# Output_Rele.net
KiCad netlist of a schematic drawn in Altium Designer
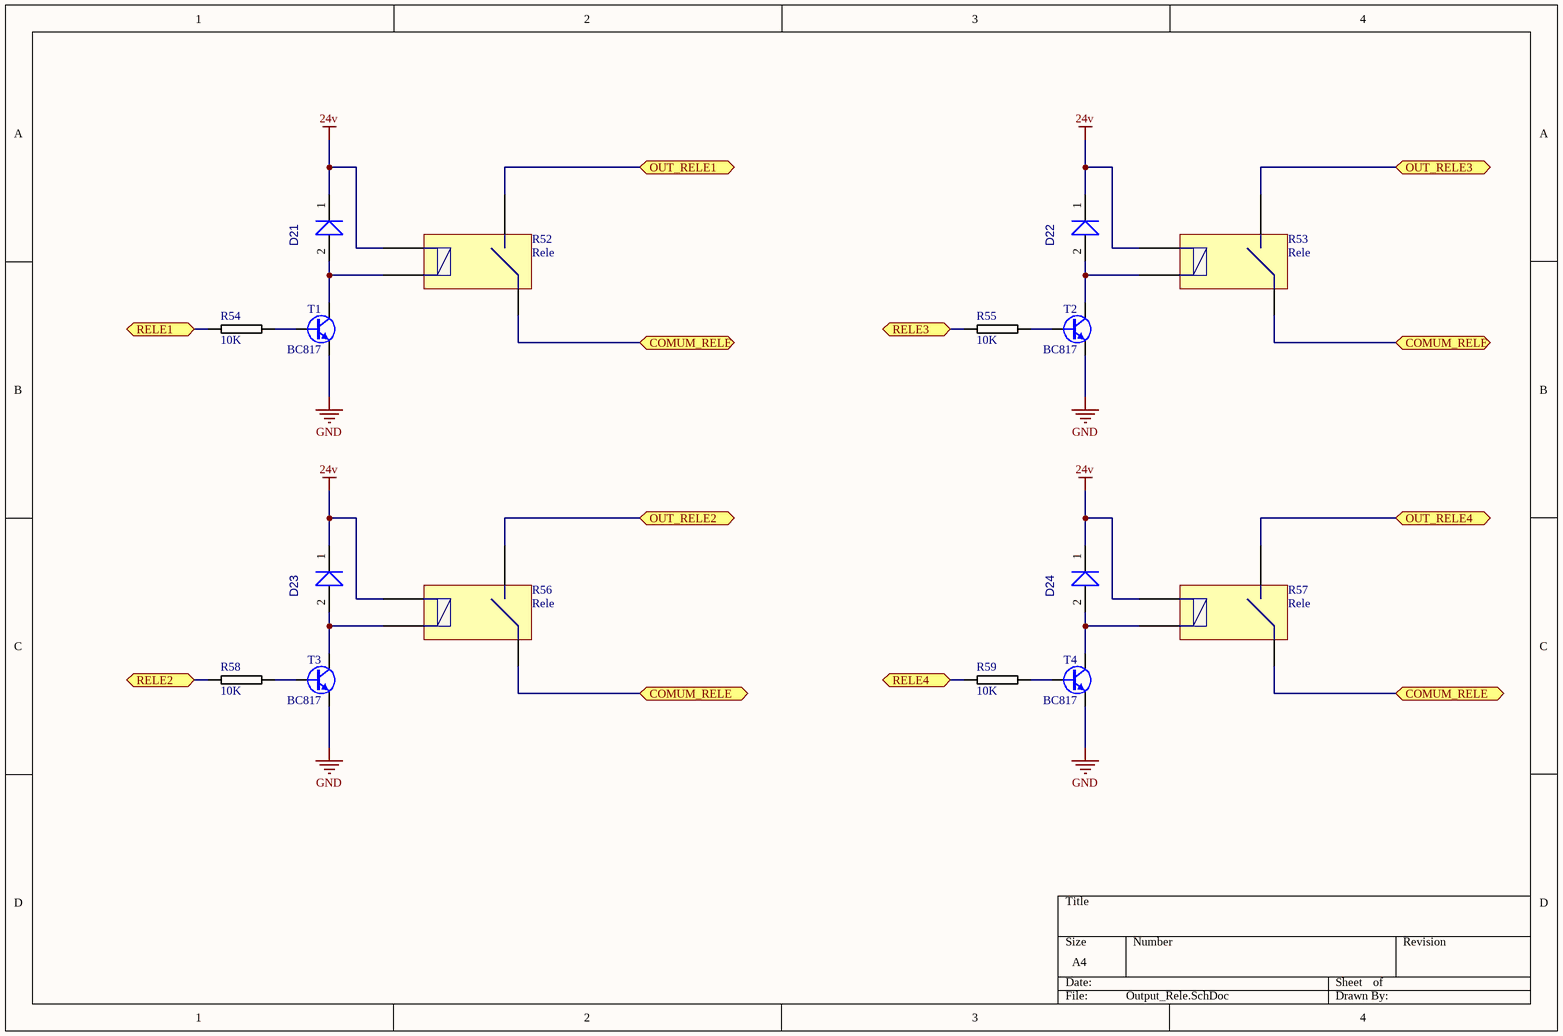
[diagram p0: Output_Rele.SchDoc]

(export (version "E")
  (design (tool "Eeschema 10.0.6"))
  (components
    (comp (ref "D21")
      (value "DIODO 1N4007 PF-B1")
      (footprint "DIODO DO41 PF-B1")
      (libsource (lib "GNATUS_COMPONENTES_BASE") (part "DIODO 1N4007 PF-B1"))
    )
    (comp (ref "D22")
      (value "DIODO 1N4007 PF-B1")
      (footprint "DIODO DO41 PF-B1")
      (libsource (lib "GNATUS_COMPONENTES_BASE") (part "DIODO 1N4007 PF-B1"))
    )
    (comp (ref "D23")
      (value "DIODO 1N4007 PF-B1")
      (footprint "DIODO DO41 PF-B1")
      (libsource (lib "GNATUS_COMPONENTES_BASE") (part "DIODO 1N4007 PF-B1"))
    )
    (comp (ref "D24")
      (value "DIODO 1N4007 PF-B1")
      (footprint "DIODO DO41 PF-B1")
      (libsource (lib "GNATUS_COMPONENTES_BASE") (part "DIODO 1N4007 PF-B1"))
    )
    (comp (ref "R52") (value "Rele") (footprint "rele") (libsource (lib "LibOlivas") (part "Rele")))
    (comp (ref "R53") (value "Rele") (footprint "rele") (libsource (lib "LibOlivas") (part "Rele")))
    (comp (ref "R54")
      (value "10K")
      (footprint "0805R-10K")
      (description "RESISTOR 0805 1/4 WATT THIN FILM")
      (libsource (lib "vh_altium_library") (part "0805R-10K"))
    )
    (comp (ref "R55")
      (value "10K")
      (footprint "0805R-10K")
      (description "RESISTOR 0805 1/4 WATT THIN FILM")
      (libsource (lib "vh_altium_library") (part "0805R-10K"))
    )
    (comp (ref "R56") (value "Rele") (footprint "rele") (libsource (lib "LibOlivas") (part "Rele")))
    (comp (ref "R57") (value "Rele") (footprint "rele") (libsource (lib "LibOlivas") (part "Rele")))
    (comp (ref "R58")
      (value "10K")
      (footprint "0805R-10K")
      (description "RESISTOR 0805 1/4 WATT THIN FILM")
      (libsource (lib "vh_altium_library") (part "0805R-10K"))
    )
    (comp (ref "R59")
      (value "10K")
      (footprint "0805R-10K")
      (description "RESISTOR 0805 1/4 WATT THIN FILM")
      (libsource (lib "vh_altium_library") (part "0805R-10K"))
    )
    (comp (ref "T1")
      (value "BC817")
      (footprint "SOT95P230X110-3N")
      (description "NPN Transistor")
      (fields (field (name "MANUFACTURER") "NXP SEMICONDUCTORS") (field (name "AUTHOR") "CERN DEM JLC"))
      (libsource (lib "ICs And Semiconductors") (part "NPN B1 E2 C3"))
    )
    (comp (ref "T2")
      (value "BC817")
      (footprint "SOT95P230X110-3N")
      (description "NPN Transistor")
      (fields (field (name "MANUFACTURER") "NXP SEMICONDUCTORS") (field (name "AUTHOR") "CERN DEM JLC"))
      (libsource (lib "ICs And Semiconductors") (part "NPN B1 E2 C3"))
    )
    (comp (ref "T3")
      (value "BC817")
      (footprint "SOT95P230X110-3N")
      (description "NPN Transistor")
      (fields (field (name "MANUFACTURER") "NXP SEMICONDUCTORS") (field (name "AUTHOR") "CERN DEM JLC"))
      (libsource (lib "ICs And Semiconductors") (part "NPN B1 E2 C3"))
    )
    (comp (ref "T4")
      (value "BC817")
      (footprint "SOT95P230X110-3N")
      (description "NPN Transistor")
      (fields (field (name "MANUFACTURER") "NXP SEMICONDUCTORS") (field (name "AUTHOR") "CERN DEM JLC"))
      (libsource (lib "ICs And Semiconductors") (part "NPN B1 E2 C3"))
    )
  )
  (nets
    (net (code "1") (name "/COMUM_RELE") (class "Default")
      (node (ref "R52") (pin "3") (pinfunction "3_3") (pintype "passive"))
      (node (ref "R53") (pin "3") (pinfunction "3_3") (pintype "passive"))
      (node (ref "R56") (pin "3") (pinfunction "3_3") (pintype "passive"))
      (node (ref "R57") (pin "3") (pinfunction "3_3") (pintype "passive"))
    )
    (net (code "2") (name "/OUT_RELE1") (class "Default")
      (node (ref "R52") (pin "4") (pinfunction "4_4") (pintype "passive"))
    )
    (net (code "3") (name "/OUT_RELE2") (class "Default")
      (node (ref "R56") (pin "4") (pinfunction "4_4") (pintype "passive"))
    )
    (net (code "4") (name "/OUT_RELE3") (class "Default")
      (node (ref "R53") (pin "4") (pinfunction "4_4") (pintype "passive"))
    )
    (net (code "5") (name "/OUT_RELE4") (class "Default")
      (node (ref "R57") (pin "4") (pinfunction "4_4") (pintype "passive"))
    )
    (net (code "6") (name "/RELE1") (class "Default") (node (ref "R54") (pin "1") (pintype "passive")))
    (net (code "7") (name "/RELE2") (class "Default") (node (ref "R58") (pin "1") (pintype "passive")))
    (net (code "8") (name "/RELE3") (class "Default") (node (ref "R55") (pin "1") (pintype "passive")))
    (net (code "9") (name "/RELE4") (class "Default") (node (ref "R59") (pin "1") (pintype "passive")))
    (net (code "10") (name "24v") (class "Default")
      (node (ref "D21") (pin "1") (pinfunction "K_1") (pintype "passive"))
      (node (ref "D22") (pin "1") (pinfunction "K_1") (pintype "passive"))
      (node (ref "D23") (pin "1") (pinfunction "K_1") (pintype "passive"))
      (node (ref "D24") (pin "1") (pinfunction "K_1") (pintype "passive"))
      (node (ref "R52") (pin "1") (pinfunction "1_1") (pintype "passive"))
      (node (ref "R53") (pin "1") (pinfunction "1_1") (pintype "passive"))
      (node (ref "R56") (pin "1") (pinfunction "1_1") (pintype "passive"))
      (node (ref "R57") (pin "1") (pinfunction "1_1") (pintype "passive"))
    )
    (net (code "11") (name "GND") (class "Default")
      (node (ref "T1") (pin "2") (pinfunction "E_2") (pintype "passive"))
      (node (ref "T2") (pin "2") (pinfunction "E_2") (pintype "passive"))
      (node (ref "T3") (pin "2") (pinfunction "E_2") (pintype "passive"))
      (node (ref "T4") (pin "2") (pinfunction "E_2") (pintype "passive"))
    )
    (net (code "12") (name "Net-(D21-A)") (class "Default")
      (node (ref "D21") (pin "2") (pinfunction "A_2") (pintype "passive"))
      (node (ref "R52") (pin "2") (pinfunction "2_2") (pintype "passive"))
      (node (ref "T1") (pin "3") (pinfunction "C_3") (pintype "passive"))
    )
    (net (code "13") (name "Net-(D22-A)") (class "Default")
      (node (ref "D22") (pin "2") (pinfunction "A_2") (pintype "passive"))
      (node (ref "R53") (pin "2") (pinfunction "2_2") (pintype "passive"))
      (node (ref "T2") (pin "3") (pinfunction "C_3") (pintype "passive"))
    )
    (net (code "14") (name "Net-(D23-A)") (class "Default")
      (node (ref "D23") (pin "2") (pinfunction "A_2") (pintype "passive"))
      (node (ref "R56") (pin "2") (pinfunction "2_2") (pintype "passive"))
      (node (ref "T3") (pin "3") (pinfunction "C_3") (pintype "passive"))
    )
    (net (code "15") (name "Net-(D24-A)") (class "Default")
      (node (ref "D24") (pin "2") (pinfunction "A_2") (pintype "passive"))
      (node (ref "R57") (pin "2") (pinfunction "2_2") (pintype "passive"))
      (node (ref "T4") (pin "3") (pinfunction "C_3") (pintype "passive"))
    )
    (net (code "16") (name "Net-(T1-B)") (class "Default")
      (node (ref "R54") (pin "2") (pintype "passive"))
      (node (ref "T1") (pin "1") (pinfunction "B_1") (pintype "passive"))
    )
    (net (code "17") (name "Net-(T2-B)") (class "Default")
      (node (ref "R55") (pin "2") (pintype "passive"))
      (node (ref "T2") (pin "1") (pinfunction "B_1") (pintype "passive"))
    )
    (net (code "18") (name "Net-(T3-B)") (class "Default")
      (node (ref "R58") (pin "2") (pintype "passive"))
      (node (ref "T3") (pin "1") (pinfunction "B_1") (pintype "passive"))
    )
    (net (code "19") (name "Net-(T4-B)") (class "Default")
      (node (ref "R59") (pin "2") (pintype "passive"))
      (node (ref "T4") (pin "1") (pinfunction "B_1") (pintype "passive"))
    )
  )
)
